# MCU_Power.net
KiCad netlist of a schematic drawn in Altium Designer
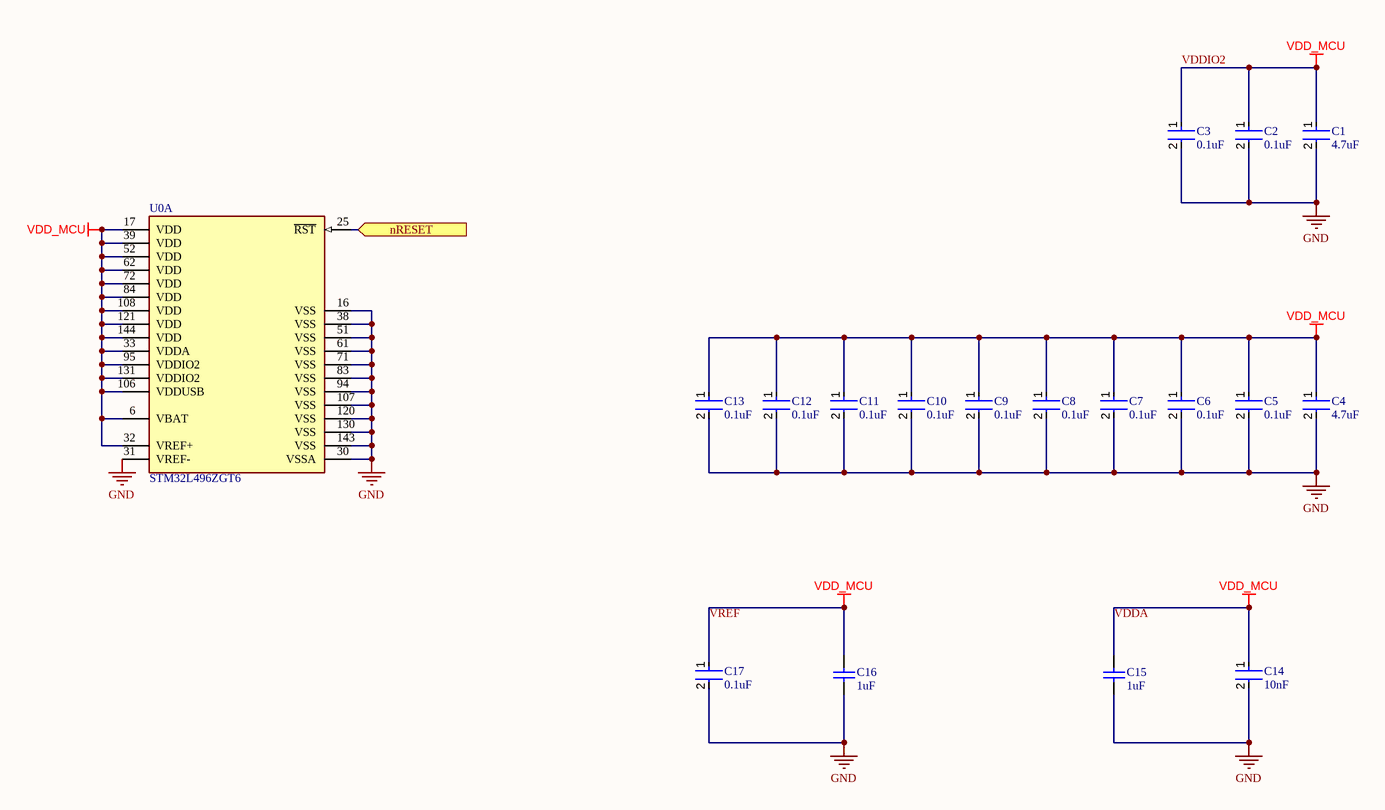
[diagram p0: MCU_Power.SchDoc]

(export (version "E")
  (design (tool "Eeschema 10.0.6"))
  (components
    (comp (ref "C1")
      (value "4.7uF")
      (footprint "FP-GRM188-0_15-IPC_A")
      (description "CAP CER 4.7UF 10V X7S 0603")
      (fields (field (name "TOLERANCE") "10%"))
      (libsource (lib "Altium Content Vault") (part "02cd4be3c70576c341d710602a673aa"))
    )
    (comp (ref "C2")
      (value "0.1uF")
      (footprint "FP-C0603C-CF-MFG")
      (description "CAP CER 0.1UF 50V X7R 0603")
      (fields (field (name "TOLERANCE") "0.1") (field (name "MANUFACTURER") "KEMET"))
      (libsource (lib "Altium Content Vault") (part "b4654b650e69147ec39a6b967a45e02"))
    )
    (comp (ref "C3")
      (value "0.1uF")
      (footprint "FP-C0603C-CF-MFG")
      (description "CAP CER 0.1UF 50V X7R 0603")
      (fields (field (name "TOLERANCE") "0.1") (field (name "MANUFACTURER") "KEMET"))
      (libsource (lib "Altium Content Vault") (part "b4654b650e69147ec39a6b967a45e02"))
    )
    (comp (ref "C4")
      (value "4.7uF")
      (footprint "FP-GRM188-0_15-IPC_A")
      (description "CAP CER 4.7UF 10V X7S 0603")
      (fields (field (name "TOLERANCE") "10%"))
      (libsource (lib "Altium Content Vault") (part "02cd4be3c70576c341d710602a673aa"))
    )
    (comp (ref "C5")
      (value "0.1uF")
      (footprint "FP-C0603C-CF-MFG")
      (description "CAP CER 0.1UF 50V X7R 0603")
      (fields (field (name "TOLERANCE") "0.1") (field (name "MANUFACTURER") "KEMET"))
      (libsource (lib "Altium Content Vault") (part "b4654b650e69147ec39a6b967a45e02"))
    )
    (comp (ref "C6")
      (value "0.1uF")
      (footprint "FP-C0603C-CF-MFG")
      (description "CAP CER 0.1UF 50V X7R 0603")
      (fields (field (name "TOLERANCE") "0.1") (field (name "MANUFACTURER") "KEMET"))
      (libsource (lib "Altium Content Vault") (part "b4654b650e69147ec39a6b967a45e02"))
    )
    (comp (ref "C7")
      (value "0.1uF")
      (footprint "FP-C0603C-CF-MFG")
      (description "CAP CER 0.1UF 50V X7R 0603")
      (fields (field (name "TOLERANCE") "0.1") (field (name "MANUFACTURER") "KEMET"))
      (libsource (lib "Altium Content Vault") (part "b4654b650e69147ec39a6b967a45e02"))
    )
    (comp (ref "C8")
      (value "0.1uF")
      (footprint "FP-C0603C-CF-MFG")
      (description "CAP CER 0.1UF 50V X7R 0603")
      (fields (field (name "TOLERANCE") "0.1") (field (name "MANUFACTURER") "KEMET"))
      (libsource (lib "Altium Content Vault") (part "b4654b650e69147ec39a6b967a45e02"))
    )
    (comp (ref "C9")
      (value "0.1uF")
      (footprint "FP-C0603C-CF-MFG")
      (description "CAP CER 0.1UF 50V X7R 0603")
      (fields (field (name "TOLERANCE") "0.1") (field (name "MANUFACTURER") "KEMET"))
      (libsource (lib "Altium Content Vault") (part "b4654b650e69147ec39a6b967a45e02"))
    )
    (comp (ref "C10")
      (value "0.1uF")
      (footprint "FP-C0603C-CF-MFG")
      (description "CAP CER 0.1UF 50V X7R 0603")
      (fields (field (name "TOLERANCE") "0.1") (field (name "MANUFACTURER") "KEMET"))
      (libsource (lib "Altium Content Vault") (part "b4654b650e69147ec39a6b967a45e02"))
    )
    (comp (ref "C11")
      (value "0.1uF")
      (footprint "FP-C0603C-CF-MFG")
      (description "CAP CER 0.1UF 50V X7R 0603")
      (fields (field (name "TOLERANCE") "0.1") (field (name "MANUFACTURER") "KEMET"))
      (libsource (lib "Altium Content Vault") (part "b4654b650e69147ec39a6b967a45e02"))
    )
    (comp (ref "C12")
      (value "0.1uF")
      (footprint "FP-C0603C-CF-MFG")
      (description "CAP CER 0.1UF 50V X7R 0603")
      (fields (field (name "TOLERANCE") "0.1") (field (name "MANUFACTURER") "KEMET"))
      (libsource (lib "Altium Content Vault") (part "b4654b650e69147ec39a6b967a45e02"))
    )
    (comp (ref "C13")
      (value "0.1uF")
      (footprint "FP-C0603C-CF-MFG")
      (description "CAP CER 0.1UF 50V X7R 0603")
      (fields (field (name "TOLERANCE") "0.1") (field (name "MANUFACTURER") "KEMET"))
      (libsource (lib "Altium Content Vault") (part "b4654b650e69147ec39a6b967a45e02"))
    )
    (comp (ref "C14")
      (value "10nF")
      (footprint "FP-GRM188-0_1-e0_2_0_5-IPC_A")
      (description "Chip Multilayer Ceramic Capacitors for General Purpose, 0603, 10000pF, X7R, 15%, 10%, 100V")
      (fields (field (name "VOLTAGE") "100V") (field (name "TOLERANCE") "10%"))
      (libsource (lib "Altium Content Vault") (part "11868f565c42a9108669ba33697ecf6"))
    )
    (comp (ref "C15")
      (value "1uF")
      (footprint "CAPC1608X90X35LL15T15")
      (fields (field (name "MANUFACTURER") "Kemet") (field (name "PART NUMBER") "C0603C105K4RACTU"))
      (libsource (lib "Altium Content Vault") (part "CAP"))
    )
    (comp (ref "C16")
      (value "1uF")
      (footprint "CAPC1608X90X35LL15T15")
      (fields (field (name "MANUFACTURER") "Kemet") (field (name "PART NUMBER") "C0603C105K4RACTU"))
      (libsource (lib "Altium Content Vault") (part "CAP"))
    )
    (comp (ref "C17")
      (value "0.1uF")
      (footprint "FP-C0603C-CF-MFG")
      (description "CAP CER 0.1UF 50V X7R 0603")
      (fields (field (name "TOLERANCE") "0.1") (field (name "MANUFACTURER") "KEMET"))
      (libsource (lib "Altium Content Vault") (part "b4654b650e69147ec39a6b967a45e02"))
    )
    (comp (ref "U0")
      (value "STM32L496ZGT6")
      (footprint "FP-LQFP144-1A-MFG")
      (description "IC MCU 32BIT 1MB FLASH 144LQFP")
      (libsource (lib "Altium Content Vault") (part "f8f598a4e7bf6abd6ff1d35fb83b48f"))
    )
  )
  (nets
    (net (code "1") (name "/nRESET") (class "Default")
      (node (ref "U0") (pin "25") (pinfunction "~{RST}_25") (pintype "input"))
    )
    (net (code "2") (name "GND") (class "Default")
      (node (ref "C1") (pin "2") (pinfunction "2_2") (pintype "passive"))
      (node (ref "C10") (pin "2") (pinfunction "2_2") (pintype "passive"))
      (node (ref "C11") (pin "2") (pinfunction "2_2") (pintype "passive"))
      (node (ref "C12") (pin "2") (pinfunction "2_2") (pintype "passive"))
      (node (ref "C13") (pin "2") (pinfunction "2_2") (pintype "passive"))
      (node (ref "C14") (pin "2") (pinfunction "2_2") (pintype "passive"))
      (node (ref "C15") (pin "1") (pinfunction "1_1") (pintype "passive"))
      (node (ref "C16") (pin "1") (pinfunction "1_1") (pintype "passive"))
      (node (ref "C17") (pin "2") (pinfunction "2_2") (pintype "passive"))
      (node (ref "C2") (pin "2") (pinfunction "2_2") (pintype "passive"))
      (node (ref "C3") (pin "2") (pinfunction "2_2") (pintype "passive"))
      (node (ref "C4") (pin "2") (pinfunction "2_2") (pintype "passive"))
      (node (ref "C5") (pin "2") (pinfunction "2_2") (pintype "passive"))
      (node (ref "C6") (pin "2") (pinfunction "2_2") (pintype "passive"))
      (node (ref "C7") (pin "2") (pinfunction "2_2") (pintype "passive"))
      (node (ref "C8") (pin "2") (pinfunction "2_2") (pintype "passive"))
      (node (ref "C9") (pin "2") (pinfunction "2_2") (pintype "passive"))
      (node (ref "U0") (pin "107") (pinfunction "VSS_107") (pintype "power_in"))
      (node (ref "U0") (pin "120") (pinfunction "VSS_120") (pintype "power_in"))
      (node (ref "U0") (pin "130") (pinfunction "VSS_130") (pintype "power_in"))
      (node (ref "U0") (pin "143") (pinfunction "VSS_143") (pintype "power_in"))
      (node (ref "U0") (pin "16") (pinfunction "VSS_16") (pintype "power_in"))
      (node (ref "U0") (pin "30") (pinfunction "VSSA_30") (pintype "power_in"))
      (node (ref "U0") (pin "31") (pinfunction "VREF-_31") (pintype "power_in"))
      (node (ref "U0") (pin "38") (pinfunction "VSS_38") (pintype "power_in"))
      (node (ref "U0") (pin "51") (pinfunction "VSS_51") (pintype "power_in"))
      (node (ref "U0") (pin "61") (pinfunction "VSS_61") (pintype "power_in"))
      (node (ref "U0") (pin "71") (pinfunction "VSS_71") (pintype "power_in"))
      (node (ref "U0") (pin "83") (pinfunction "VSS_83") (pintype "power_in"))
      (node (ref "U0") (pin "94") (pinfunction "VSS_94") (pintype "power_in"))
    )
    (net (code "3") (name "VDD_MCU") (class "Default")
      (node (ref "C1") (pin "1") (pinfunction "1_1") (pintype "passive"))
      (node (ref "C10") (pin "1") (pinfunction "1_1") (pintype "passive"))
      (node (ref "C11") (pin "1") (pinfunction "1_1") (pintype "passive"))
      (node (ref "C12") (pin "1") (pinfunction "1_1") (pintype "passive"))
      (node (ref "C13") (pin "1") (pinfunction "1_1") (pintype "passive"))
      (node (ref "C14") (pin "1") (pinfunction "1_1") (pintype "passive"))
      (node (ref "C15") (pin "2") (pinfunction "2_2") (pintype "passive"))
      (node (ref "C16") (pin "2") (pinfunction "2_2") (pintype "passive"))
      (node (ref "C17") (pin "1") (pinfunction "1_1") (pintype "passive"))
      (node (ref "C2") (pin "1") (pinfunction "1_1") (pintype "passive"))
      (node (ref "C3") (pin "1") (pinfunction "1_1") (pintype "passive"))
      (node (ref "C4") (pin "1") (pinfunction "1_1") (pintype "passive"))
      (node (ref "C5") (pin "1") (pinfunction "1_1") (pintype "passive"))
      (node (ref "C6") (pin "1") (pinfunction "1_1") (pintype "passive"))
      (node (ref "C7") (pin "1") (pinfunction "1_1") (pintype "passive"))
      (node (ref "C8") (pin "1") (pinfunction "1_1") (pintype "passive"))
      (node (ref "C9") (pin "1") (pinfunction "1_1") (pintype "passive"))
      (node (ref "U0") (pin "106") (pinfunction "VDDUSB_106") (pintype "power_in"))
      (node (ref "U0") (pin "108") (pinfunction "VDD_108") (pintype "power_in"))
      (node (ref "U0") (pin "121") (pinfunction "VDD_121") (pintype "power_in"))
      (node (ref "U0") (pin "131") (pinfunction "VDDIO2_131") (pintype "power_in"))
      (node (ref "U0") (pin "144") (pinfunction "VDD_144") (pintype "power_in"))
      (node (ref "U0") (pin "17") (pinfunction "VDD_17") (pintype "power_in"))
      (node (ref "U0") (pin "32") (pinfunction "VREF+_32") (pintype "power_in"))
      (node (ref "U0") (pin "33") (pinfunction "VDDA_33") (pintype "power_in"))
      (node (ref "U0") (pin "39") (pinfunction "VDD_39") (pintype "power_in"))
      (node (ref "U0") (pin "52") (pinfunction "VDD_52") (pintype "power_in"))
      (node (ref "U0") (pin "6") (pinfunction "VBAT_6") (pintype "power_in"))
      (node (ref "U0") (pin "62") (pinfunction "VDD_62") (pintype "power_in"))
      (node (ref "U0") (pin "72") (pinfunction "VDD_72") (pintype "power_in"))
      (node (ref "U0") (pin "84") (pinfunction "VDD_84") (pintype "power_in"))
      (node (ref "U0") (pin "95") (pinfunction "VDDIO2_95") (pintype "power_in"))
    )
  )
)
